# rfid.net
KiCad netlist of a schematic drawn in EAGLE
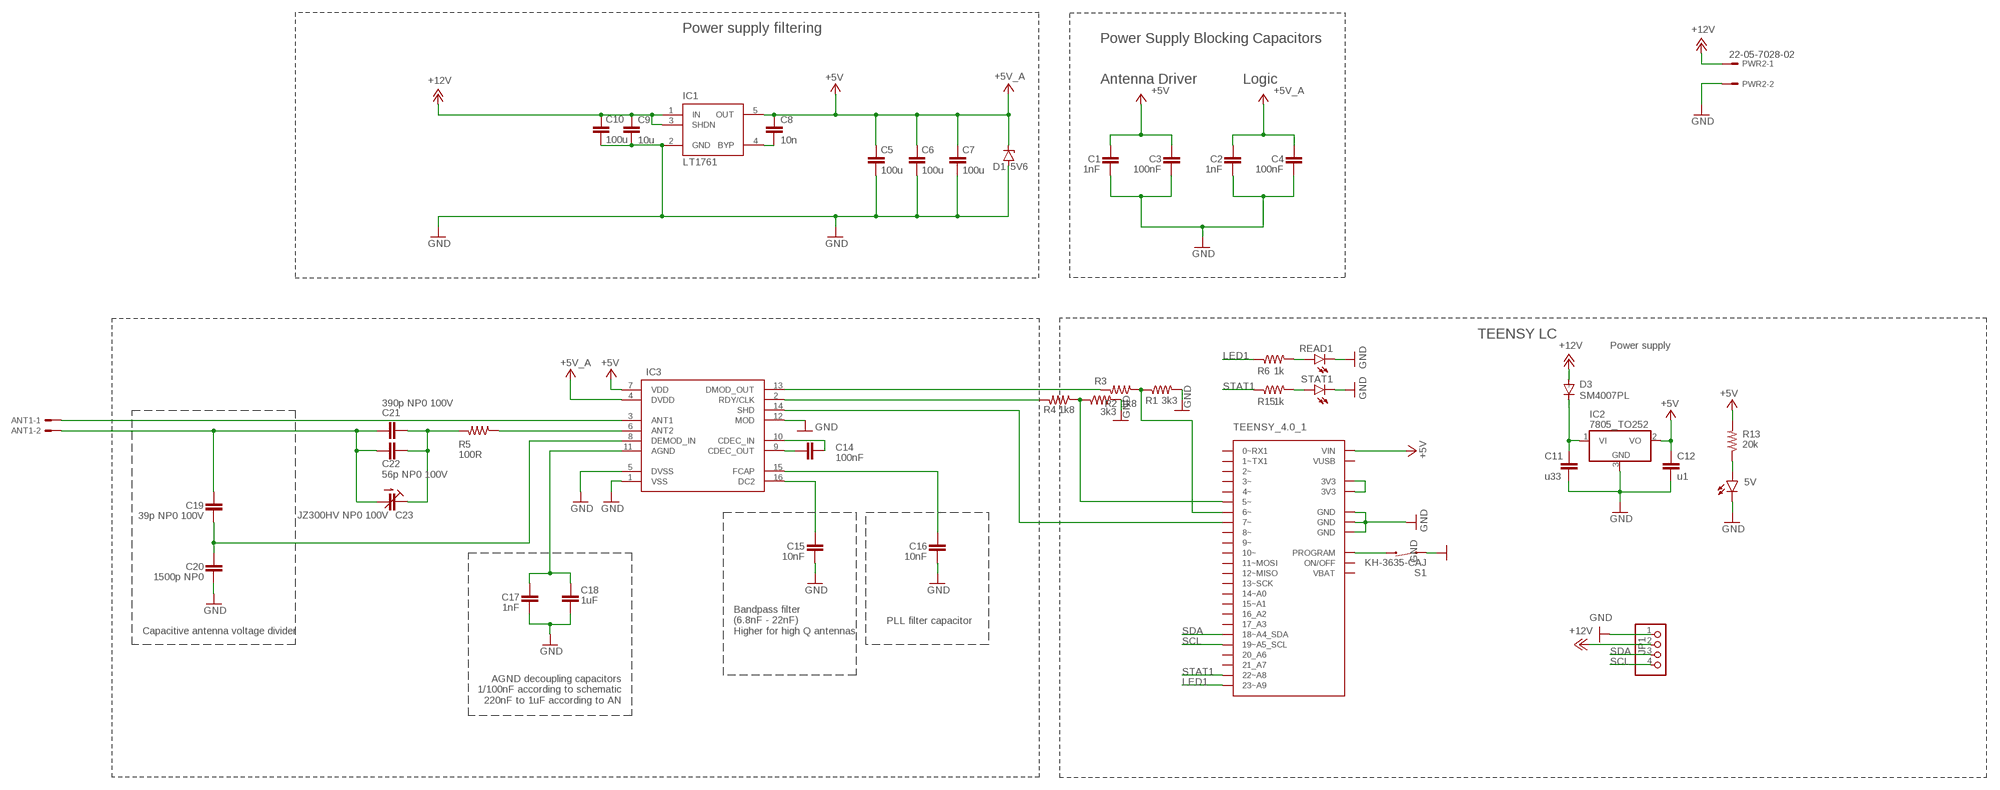
[diagram p0: schematic, sheet 1, part 1 of 2]
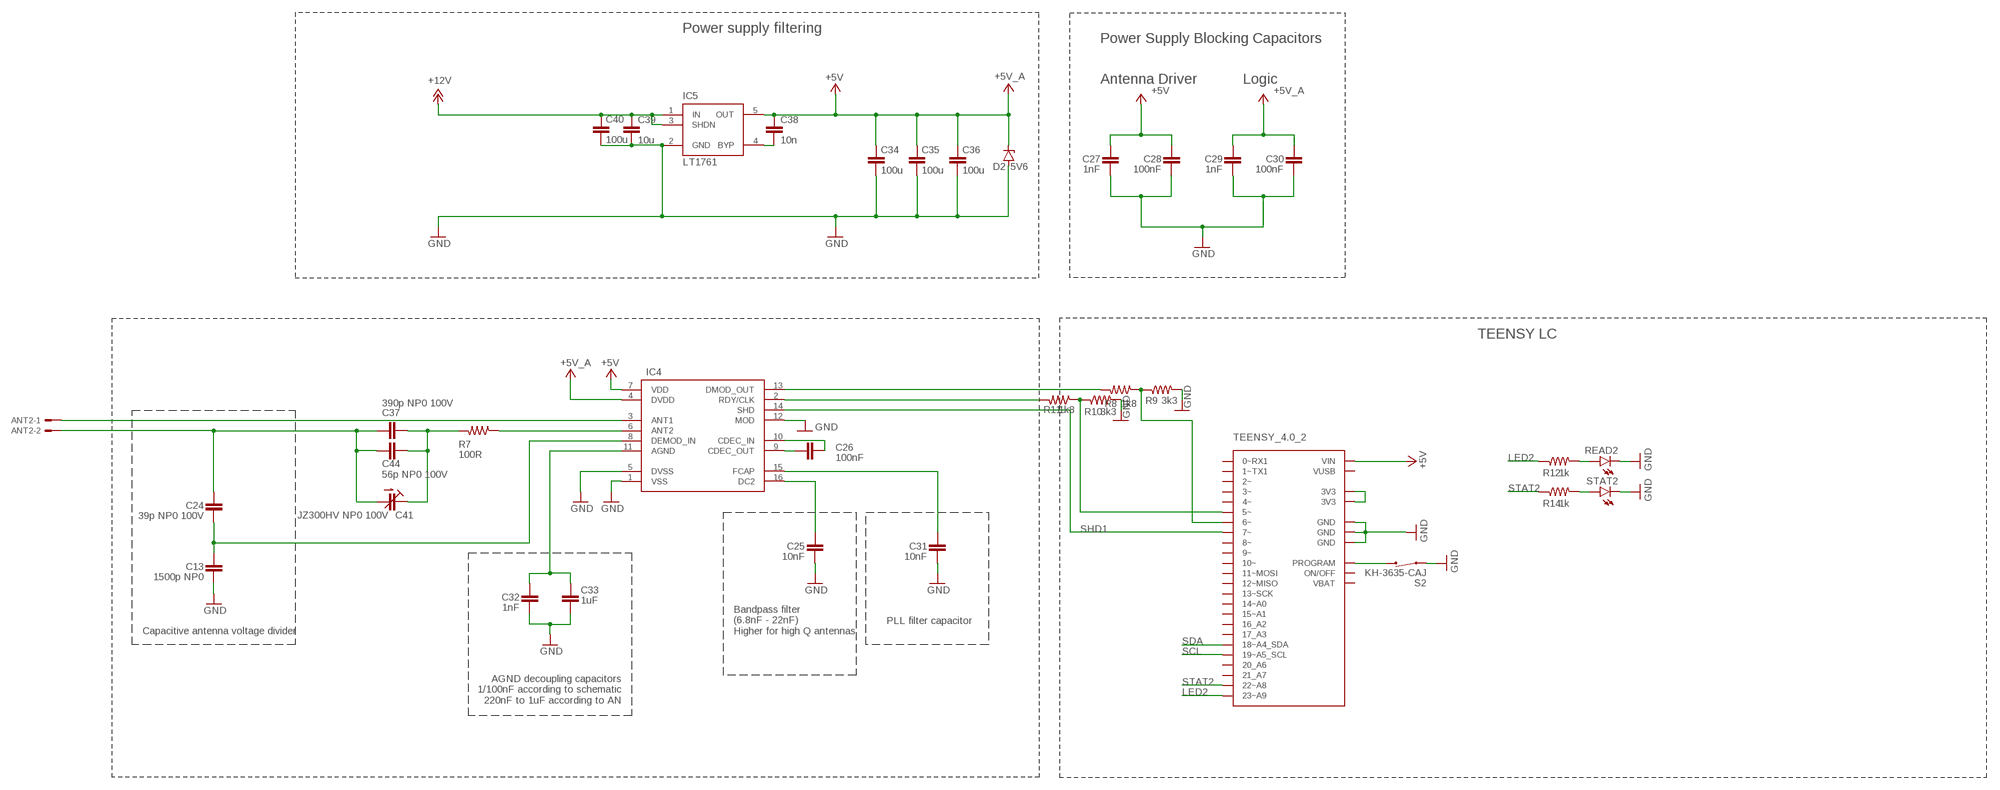
[diagram p1: schematic, sheet 1, part 2 of 2]

(export (version "E")
  (design (tool "Eeschema 10.0.6"))
  (components
    (comp (ref "5V")
      (value "LEDCHIPLED_0805")
      (footprint "eagle-import:CHIPLED_0805")
      (libsource (lib "eagle-import") (part "LEDCHIPLED_0805"))
    )
    (comp (ref "ANT1")
      (value "53261-02")
      (footprint "eagle-import:53261-02")
      (fields (field (name "MF") "MOLEX"))
      (libsource (lib "eagle-import") (part "53?-02261"))
    )
    (comp (ref "ANT2")
      (value "53261-02")
      (footprint "eagle-import:53261-02")
      (fields (field (name "MF") "MOLEX"))
      (libsource (lib "eagle-import") (part "53?-02261"))
    )
    (comp (ref "C1")
      (value "1nF")
      (footprint "eagle-import:R1206")
      (libsource (lib "eagle-import") (part "C1206"))
    )
    (comp (ref "C2")
      (value "1nF")
      (footprint "eagle-import:R1206")
      (libsource (lib "eagle-import") (part "C1206"))
    )
    (comp (ref "C3")
      (value "100nF")
      (footprint "eagle-import:R1206")
      (libsource (lib "eagle-import") (part "C1206"))
    )
    (comp (ref "C4")
      (value "100nF")
      (footprint "eagle-import:R1206")
      (libsource (lib "eagle-import") (part "C1206"))
    )
    (comp (ref "C5")
      (value "100u")
      (footprint "eagle-import:R1206")
      (libsource (lib "eagle-import") (part "C1206"))
    )
    (comp (ref "C6")
      (value "100u")
      (footprint "eagle-import:R1206")
      (libsource (lib "eagle-import") (part "C1206"))
    )
    (comp (ref "C7")
      (value "100u")
      (footprint "eagle-import:R1206")
      (libsource (lib "eagle-import") (part "C1206"))
    )
    (comp (ref "C8")
      (value "10n")
      (footprint "eagle-import:R1206")
      (libsource (lib "eagle-import") (part "C1206"))
    )
    (comp (ref "C9")
      (value "10u")
      (footprint "eagle-import:R1206")
      (libsource (lib "eagle-import") (part "C1206"))
    )
    (comp (ref "C10")
      (value "100u")
      (footprint "eagle-import:R1206")
      (libsource (lib "eagle-import") (part "C1206"))
    )
    (comp (ref "C11")
      (value "u33")
      (footprint "eagle-import:C0805")
      (libsource (lib "eagle-import") (part "C-EUC0805"))
    )
    (comp (ref "C12")
      (value "u1")
      (footprint "eagle-import:C0805")
      (libsource (lib "eagle-import") (part "C-EUC0805"))
    )
    (comp (ref "C13")
      (value "1500p NP0")
      (footprint "eagle-import:R1206")
      (libsource (lib "eagle-import") (part "C1206"))
    )
    (comp (ref "C14")
      (value "100nF")
      (footprint "eagle-import:R1206")
      (libsource (lib "eagle-import") (part "C1206"))
    )
    (comp (ref "C15")
      (value "10nF")
      (footprint "eagle-import:R1206")
      (libsource (lib "eagle-import") (part "C1206"))
    )
    (comp (ref "C16")
      (value "10nF")
      (footprint "eagle-import:R1206")
      (libsource (lib "eagle-import") (part "C1206"))
    )
    (comp (ref "C17")
      (value "1nF")
      (footprint "eagle-import:R1206")
      (libsource (lib "eagle-import") (part "C1206"))
    )
    (comp (ref "C18")
      (value "1uF")
      (footprint "eagle-import:R1206")
      (libsource (lib "eagle-import") (part "C1206"))
    )
    (comp (ref "C19")
      (value "39p NP0 100V")
      (footprint "eagle-import:R1206")
      (libsource (lib "eagle-import") (part "C1206"))
    )
    (comp (ref "C20")
      (value "1500p NP0")
      (footprint "eagle-import:R1206")
      (libsource (lib "eagle-import") (part "C1206"))
    )
    (comp (ref "C21")
      (value "390p NP0 100V")
      (footprint "eagle-import:R1206")
      (libsource (lib "eagle-import") (part "C1206"))
    )
    (comp (ref "C22")
      (value "56p NP0 100V")
      (footprint "eagle-import:R1206")
      (libsource (lib "eagle-import") (part "C1206"))
    )
    (comp (ref "C23")
      (value "JZ300HV NP0 100V")
      (footprint "eagle-import:JZ300HV")
      (libsource (lib "eagle-import") (part "JZ300HV"))
    )
    (comp (ref "C24")
      (value "39p NP0 100V")
      (footprint "eagle-import:R1206")
      (libsource (lib "eagle-import") (part "C1206"))
    )
    (comp (ref "C25")
      (value "10nF")
      (footprint "eagle-import:R1206")
      (libsource (lib "eagle-import") (part "C1206"))
    )
    (comp (ref "C26")
      (value "100nF")
      (footprint "eagle-import:R1206")
      (libsource (lib "eagle-import") (part "C1206"))
    )
    (comp (ref "C27")
      (value "1nF")
      (footprint "eagle-import:R1206")
      (libsource (lib "eagle-import") (part "C1206"))
    )
    (comp (ref "C28")
      (value "100nF")
      (footprint "eagle-import:R1206")
      (libsource (lib "eagle-import") (part "C1206"))
    )
    (comp (ref "C29")
      (value "1nF")
      (footprint "eagle-import:R1206")
      (libsource (lib "eagle-import") (part "C1206"))
    )
    (comp (ref "C30")
      (value "100nF")
      (footprint "eagle-import:R1206")
      (libsource (lib "eagle-import") (part "C1206"))
    )
    (comp (ref "C31")
      (value "10nF")
      (footprint "eagle-import:R1206")
      (libsource (lib "eagle-import") (part "C1206"))
    )
    (comp (ref "C32")
      (value "1nF")
      (footprint "eagle-import:R1206")
      (libsource (lib "eagle-import") (part "C1206"))
    )
    (comp (ref "C33")
      (value "1uF")
      (footprint "eagle-import:R1206")
      (libsource (lib "eagle-import") (part "C1206"))
    )
    (comp (ref "C34")
      (value "100u")
      (footprint "eagle-import:R1206")
      (libsource (lib "eagle-import") (part "C1206"))
    )
    (comp (ref "C35")
      (value "100u")
      (footprint "eagle-import:R1206")
      (libsource (lib "eagle-import") (part "C1206"))
    )
    (comp (ref "C36")
      (value "100u")
      (footprint "eagle-import:R1206")
      (libsource (lib "eagle-import") (part "C1206"))
    )
    (comp (ref "C37")
      (value "390p NP0 100V")
      (footprint "eagle-import:R1206")
      (libsource (lib "eagle-import") (part "C1206"))
    )
    (comp (ref "C38")
      (value "10n")
      (footprint "eagle-import:R1206")
      (libsource (lib "eagle-import") (part "C1206"))
    )
    (comp (ref "C39")
      (value "10u")
      (footprint "eagle-import:R1206")
      (libsource (lib "eagle-import") (part "C1206"))
    )
    (comp (ref "C40")
      (value "100u")
      (footprint "eagle-import:R1206")
      (libsource (lib "eagle-import") (part "C1206"))
    )
    (comp (ref "C41")
      (value "JZ300HV NP0 100V")
      (footprint "eagle-import:JZ300HV")
      (libsource (lib "eagle-import") (part "JZ300HV"))
    )
    (comp (ref "C44")
      (value "56p NP0 100V")
      (footprint "eagle-import:R1206")
      (libsource (lib "eagle-import") (part "C1206"))
    )
    (comp (ref "D1")
      (value "5V6")
      (footprint "eagle-import:SOD80C")
      (libsource (lib "eagle-import") (part "ZENER-DIODESOD80C"))
    )
    (comp (ref "D2")
      (value "5V6")
      (footprint "eagle-import:SOD80C")
      (libsource (lib "eagle-import") (part "ZENER-DIODESOD80C"))
    )
    (comp (ref "D3")
      (value "SM4007PL")
      (footprint "eagle-import:SOD-123_MINI-SMA")
      (libsource (lib "eagle-import") (part "CGRM400-G7"))
    )
    (comp (ref "IC1")
      (value "LT1761")
      (footprint "eagle-import:TSOT23-5")
      (libsource (lib "eagle-import") (part "LT1761"))
    )
    (comp (ref "IC2")
      (value "7805_TO252")
      (footprint "eagle-import:TO252")
      (libsource (lib "eagle-import") (part "7805_TO252"))
    )
    (comp (ref "IC3")
      (value "EM4095")
      (footprint "eagle-import:SO16")
      (libsource (lib "eagle-import") (part "EM4095"))
    )
    (comp (ref "IC4")
      (value "EM4095")
      (footprint "eagle-import:SO16")
      (libsource (lib "eagle-import") (part "EM4095"))
    )
    (comp (ref "IC5")
      (value "LT1761")
      (footprint "eagle-import:TSOT23-5")
      (libsource (lib "eagle-import") (part "LT1761"))
    )
    (comp (ref "JP1")
      (value "PINHD-1X4")
      (footprint "eagle-import:1X04")
      (libsource (lib "eagle-import") (part "PINHD-1X4"))
    )
    (comp (ref "PWR2")
      (value "22-05-7028-02")
      (footprint "eagle-import:7395-02")
      (fields (field (name "MF") "MOLEX"))
      (libsource (lib "eagle-import") (part "22-?-0205-7028"))
    )
    (comp (ref "R1")
      (value "3k3")
      (footprint "eagle-import:R0805")
      (libsource (lib "eagle-import") (part "R-US_R0805"))
    )
    (comp (ref "R2")
      (value "1k8")
      (footprint "eagle-import:R0805")
      (libsource (lib "eagle-import") (part "R-US_R0805"))
    )
    (comp (ref "R3")
      (value "3k3")
      (footprint "eagle-import:R0805")
      (libsource (lib "eagle-import") (part "R-US_R0805"))
    )
    (comp (ref "R4")
      (value "1k8")
      (footprint "eagle-import:R0805")
      (libsource (lib "eagle-import") (part "R-US_R0805"))
    )
    (comp (ref "R5")
      (value "100R")
      (footprint "eagle-import:R1206")
      (libsource (lib "eagle-import") (part "R1206"))
    )
    (comp (ref "R6")
      (value "1k")
      (footprint "eagle-import:R0805")
      (libsource (lib "eagle-import") (part "R-US_R0805"))
    )
    (comp (ref "R7")
      (value "100R")
      (footprint "eagle-import:R1206")
      (libsource (lib "eagle-import") (part "R1206"))
    )
    (comp (ref "R8")
      (value "1k8")
      (footprint "eagle-import:R0805")
      (libsource (lib "eagle-import") (part "R-US_R0805"))
    )
    (comp (ref "R9")
      (value "3k3")
      (footprint "eagle-import:R0805")
      (libsource (lib "eagle-import") (part "R-US_R0805"))
    )
    (comp (ref "R10")
      (value "3k3")
      (footprint "eagle-import:R0805")
      (libsource (lib "eagle-import") (part "R-US_R0805"))
    )
    (comp (ref "R11")
      (value "1k8")
      (footprint "eagle-import:R0805")
      (libsource (lib "eagle-import") (part "R-US_R0805"))
    )
    (comp (ref "R12")
      (value "1k")
      (footprint "eagle-import:R0805")
      (libsource (lib "eagle-import") (part "R-US_R0805"))
    )
    (comp (ref "R13")
      (value "20k")
      (footprint "eagle-import:R0805")
      (libsource (lib "eagle-import") (part "R-US_R0805"))
    )
    (comp (ref "R14")
      (value "1k")
      (footprint "eagle-import:R0805")
      (libsource (lib "eagle-import") (part "R-US_R0805"))
    )
    (comp (ref "R15")
      (value "1k")
      (footprint "eagle-import:R0805")
      (libsource (lib "eagle-import") (part "R-US_R0805"))
    )
    (comp (ref "READ1")
      (value "LEDCHIPLED_0805")
      (footprint "eagle-import:CHIPLED_0805")
      (libsource (lib "eagle-import") (part "LEDCHIPLED_0805"))
    )
    (comp (ref "READ2")
      (value "LEDCHIPLED_0805")
      (footprint "eagle-import:CHIPLED_0805")
      (libsource (lib "eagle-import") (part "LEDCHIPLED_0805"))
    )
    (comp (ref "S1")
      (value "KH-3635-CAJ")
      (footprint "eagle-import:KH-3635-CAJ")
      (libsource (lib "eagle-import") (part "KH-3635-CAJ"))
    )
    (comp (ref "S2")
      (value "KH-3635-CAJ")
      (footprint "eagle-import:KH-3635-CAJ")
      (libsource (lib "eagle-import") (part "KH-3635-CAJ"))
    )
    (comp (ref "STAT1")
      (value "LEDCHIPLED_0805")
      (footprint "eagle-import:CHIPLED_0805")
      (libsource (lib "eagle-import") (part "LEDCHIPLED_0805"))
    )
    (comp (ref "STAT2")
      (value "LEDCHIPLED_0805")
      (footprint "eagle-import:CHIPLED_0805")
      (libsource (lib "eagle-import") (part "LEDCHIPLED_0805"))
    )
    (comp (ref "TEENSY_4.0_1")
      (value "TEENSY40")
      (footprint "eagle-import:TEENSY40")
      (libsource (lib "eagle-import") (part "TEENSY40"))
    )
    (comp (ref "TEENSY_4.0_2")
      (value "TEENSY40")
      (footprint "eagle-import:TEENSY40")
      (libsource (lib "eagle-import") (part "TEENSY40"))
    )
  )
  (nets
    (net (code "1") (name "+5V") (class "Default")
      (node (ref "C1") (pin "2") (pinfunction "2_2") (pintype "passive"))
      (node (ref "C12") (pin "1") (pinfunction "1_1") (pintype "passive"))
      (node (ref "C2") (pin "2") (pinfunction "2_2") (pintype "passive"))
      (node (ref "C27") (pin "2") (pinfunction "2_2") (pintype "passive"))
      (node (ref "C28") (pin "2") (pinfunction "2_2") (pintype "passive"))
      (node (ref "C29") (pin "2") (pinfunction "2_2") (pintype "passive"))
      (node (ref "C3") (pin "2") (pinfunction "2_2") (pintype "passive"))
      (node (ref "C30") (pin "2") (pinfunction "2_2") (pintype "passive"))
      (node (ref "C34") (pin "1") (pinfunction "1_1") (pintype "passive"))
      (node (ref "C35") (pin "1") (pinfunction "1_1") (pintype "passive"))
      (node (ref "C36") (pin "1") (pinfunction "1_1") (pintype "passive"))
      (node (ref "C38") (pin "1") (pinfunction "1_1") (pintype "passive"))
      (node (ref "C4") (pin "2") (pinfunction "2_2") (pintype "passive"))
      (node (ref "C5") (pin "1") (pinfunction "1_1") (pintype "passive"))
      (node (ref "C6") (pin "1") (pinfunction "1_1") (pintype "passive"))
      (node (ref "C7") (pin "1") (pinfunction "1_1") (pintype "passive"))
      (node (ref "C8") (pin "1") (pinfunction "1_1") (pintype "passive"))
      (node (ref "D1") (pin "C") (pinfunction "C_C") (pintype "passive"))
      (node (ref "D2") (pin "C") (pinfunction "C_C") (pintype "passive"))
      (node (ref "IC1") (pin "5") (pinfunction "OUT_5") (pintype "power_in"))
      (node (ref "IC2") (pin "2") (pinfunction "VO_2") (pintype "passive"))
      (node (ref "IC3") (pin "4") (pinfunction "DVDD_4") (pintype "power_in"))
      (node (ref "IC3") (pin "7") (pinfunction "VDD_7") (pintype "power_in"))
      (node (ref "IC4") (pin "4") (pinfunction "DVDD_4") (pintype "power_in"))
      (node (ref "IC4") (pin "7") (pinfunction "VDD_7") (pintype "power_in"))
      (node (ref "IC5") (pin "5") (pinfunction "OUT_5") (pintype "power_in"))
      (node (ref "R13") (pin "2") (pinfunction "2_2") (pintype "passive"))
      (node (ref "TEENSY_4.0_1") (pin "VIN") (pinfunction "VIN_VIN") (pintype "bidirectional"))
      (node (ref "TEENSY_4.0_2") (pin "VIN") (pinfunction "VIN_VIN") (pintype "bidirectional"))
    )
    (net (code "2") (name "+12V") (class "Default")
      (node (ref "C10") (pin "1") (pinfunction "1_1") (pintype "passive"))
      (node (ref "C39") (pin "1") (pinfunction "1_1") (pintype "passive"))
      (node (ref "C40") (pin "1") (pinfunction "1_1") (pintype "passive"))
      (node (ref "C9") (pin "1") (pinfunction "1_1") (pintype "passive"))
      (node (ref "D3") (pin "A") (pinfunction "A_A") (pintype "passive"))
      (node (ref "IC1") (pin "1") (pinfunction "IN_1") (pintype "power_in"))
      (node (ref "IC1") (pin "3") (pinfunction "SHDN_3") (pintype "input"))
      (node (ref "IC5") (pin "1") (pinfunction "IN_1") (pintype "power_in"))
      (node (ref "IC5") (pin "3") (pinfunction "SHDN_3") (pintype "input"))
      (node (ref "JP1") (pin "2") (pinfunction "2_2") (pintype "passive"))
      (node (ref "PWR2") (pin "1") (pinfunction "S_1") (pintype "passive"))
    )
    (net (code "3") (name "/LED1") (class "Default")
      (node (ref "R6") (pin "1") (pinfunction "1_1") (pintype "passive"))
      (node (ref "TEENSY_4.0_1") (pin "23") (pinfunction "23~{A9}_23") (pintype "bidirectional"))
    )
    (net (code "4") (name "/LED2") (class "Default")
      (node (ref "R12") (pin "1") (pinfunction "1_1") (pintype "passive"))
      (node (ref "TEENSY_4.0_2") (pin "23") (pinfunction "23~{A9}_23") (pintype "bidirectional"))
    )
    (net (code "5") (name "/SCL") (class "Default")
      (node (ref "JP1") (pin "4") (pinfunction "4_4") (pintype "passive"))
      (node (ref "TEENSY_4.0_1") (pin "19") (pinfunction "19~{A5_SCL}_19") (pintype "bidirectional"))
      (node (ref "TEENSY_4.0_2") (pin "19") (pinfunction "19~{A5_SCL}_19") (pintype "bidirectional"))
    )
    (net (code "6") (name "/SDA") (class "Default")
      (node (ref "JP1") (pin "3") (pinfunction "3_3") (pintype "passive"))
      (node (ref "TEENSY_4.0_1") (pin "18") (pinfunction "18~{A4_SDA}_18") (pintype "bidirectional"))
      (node (ref "TEENSY_4.0_2") (pin "18") (pinfunction "18~{A4_SDA}_18") (pintype "bidirectional"))
    )
    (net (code "7") (name "/SHD1") (class "Default")
      (node (ref "IC4") (pin "14") (pinfunction "SHD_14") (pintype "input"))
      (node (ref "TEENSY_4.0_2") (pin "7") (pinfunction "7~{}_7") (pintype "bidirectional"))
    )
    (net (code "8") (name "/STAT1") (class "Default")
      (node (ref "R15") (pin "1") (pinfunction "1_1") (pintype "passive"))
      (node (ref "TEENSY_4.0_1") (pin "22") (pinfunction "22~{A8}_22") (pintype "bidirectional"))
    )
    (net (code "9") (name "/STAT2") (class "Default")
      (node (ref "R14") (pin "1") (pinfunction "1_1") (pintype "passive"))
      (node (ref "TEENSY_4.0_2") (pin "22") (pinfunction "22~{A8}_22") (pintype "bidirectional"))
    )
    (net (code "10") (name "GND") (class "Default")
      (node (ref "5V") (pin "C") (pinfunction "C_C") (pintype "passive"))
      (node (ref "C1") (pin "1") (pinfunction "1_1") (pintype "passive"))
      (node (ref "C10") (pin "2") (pinfunction "2_2") (pintype "passive"))
      (node (ref "C11") (pin "2") (pinfunction "2_2") (pintype "passive"))
      (node (ref "C12") (pin "2") (pinfunction "2_2") (pintype "passive"))
      (node (ref "C13") (pin "1") (pinfunction "1_1") (pintype "passive"))
      (node (ref "C15") (pin "2") (pinfunction "2_2") (pintype "passive"))
      (node (ref "C16") (pin "2") (pinfunction "2_2") (pintype "passive"))
      (node (ref "C17") (pin "1") (pinfunction "1_1") (pintype "passive"))
      (node (ref "C18") (pin "1") (pinfunction "1_1") (pintype "passive"))
      (node (ref "C2") (pin "1") (pinfunction "1_1") (pintype "passive"))
      (node (ref "C20") (pin "1") (pinfunction "1_1") (pintype "passive"))
      (node (ref "C25") (pin "2") (pinfunction "2_2") (pintype "passive"))
      (node (ref "C27") (pin "1") (pinfunction "1_1") (pintype "passive"))
      (node (ref "C28") (pin "1") (pinfunction "1_1") (pintype "passive"))
      (node (ref "C29") (pin "1") (pinfunction "1_1") (pintype "passive"))
      (node (ref "C3") (pin "1") (pinfunction "1_1") (pintype "passive"))
      (node (ref "C30") (pin "1") (pinfunction "1_1") (pintype "passive"))
      (node (ref "C31") (pin "2") (pinfunction "2_2") (pintype "passive"))
      (node (ref "C32") (pin "1") (pinfunction "1_1") (pintype "passive"))
      (node (ref "C33") (pin "1") (pinfunction "1_1") (pintype "passive"))
      (node (ref "C34") (pin "2") (pinfunction "2_2") (pintype "passive"))
      (node (ref "C35") (pin "2") (pinfunction "2_2") (pintype "passive"))
      (node (ref "C36") (pin "2") (pinfunction "2_2") (pintype "passive"))
      (node (ref "C39") (pin "2") (pinfunction "2_2") (pintype "passive"))
      (node (ref "C4") (pin "1") (pinfunction "1_1") (pintype "passive"))
      (node (ref "C40") (pin "2") (pinfunction "2_2") (pintype "passive"))
      (node (ref "C5") (pin "2") (pinfunction "2_2") (pintype "passive"))
      (node (ref "C6") (pin "2") (pinfunction "2_2") (pintype "passive"))
      (node (ref "C7") (pin "2") (pinfunction "2_2") (pintype "passive"))
      (node (ref "C9") (pin "2") (pinfunction "2_2") (pintype "passive"))
      (node (ref "D1") (pin "A") (pinfunction "A_A") (pintype "passive"))
      (node (ref "D2") (pin "A") (pinfunction "A_A") (pintype "passive"))
      (node (ref "IC1") (pin "2") (pinfunction "GND_2") (pintype "power_in"))
      (node (ref "IC2") (pin "3") (pinfunction "GND_3") (pintype "passive"))
      (node (ref "IC3") (pin "1") (pinfunction "VSS_1") (pintype "power_in"))
      (node (ref "IC3") (pin "12") (pinfunction "MOD_12") (pintype "input"))
      (node (ref "IC3") (pin "5") (pinfunction "DVSS_5") (pintype "power_in"))
      (node (ref "IC4") (pin "1") (pinfunction "VSS_1") (pintype "power_in"))
      (node (ref "IC4") (pin "12") (pinfunction "MOD_12") (pintype "input"))
      (node (ref "IC4") (pin "5") (pinfunction "DVSS_5") (pintype "power_in"))
      (node (ref "IC5") (pin "2") (pinfunction "GND_2") (pintype "power_in"))
      (node (ref "JP1") (pin "1") (pinfunction "1_1") (pintype "passive"))
      (node (ref "PWR2") (pin "2") (pinfunction "S_2") (pintype "passive"))
      (node (ref "R1") (pin "2") (pinfunction "2_2") (pintype "passive"))
      (node (ref "R10") (pin "2") (pinfunction "2_2") (pintype "passive"))
      (node (ref "R3") (pin "2") (pinfunction "2_2") (pintype "passive"))
      (node (ref "R9") (pin "2") (pinfunction "2_2") (pintype "passive"))
      (node (ref "READ1") (pin "C") (pinfunction "C_C") (pintype "passive"))
      (node (ref "READ2") (pin "C") (pinfunction "C_C") (pintype "passive"))
      (node (ref "S1") (pin "P$1") (pinfunction "1_P$1") (pintype "passive"))
      (node (ref "S2") (pin "P$1") (pinfunction "1_P$1") (pintype "passive"))
      (node (ref "STAT1") (pin "C") (pinfunction "C_C") (pintype "passive"))
      (node (ref "STAT2") (pin "C") (pinfunction "C_C") (pintype "passive"))
      (node (ref "TEENSY_4.0_1") (pin "GND") (pinfunction "GND_GND") (pintype "bidirectional"))
      (node (ref "TEENSY_4.0_1") (pin "GND@1") (pinfunction "GND_GND@1") (pintype "bidirectional"))
      (node (ref "TEENSY_4.0_1") (pin "GND@2") (pinfunction "GND_GND@2") (pintype "bidirectional"))
      (node (ref "TEENSY_4.0_2") (pin "GND") (pinfunction "GND_GND") (pintype "bidirectional"))
      (node (ref "TEENSY_4.0_2") (pin "GND@1") (pinfunction "GND_GND@1") (pintype "bidirectional"))
      (node (ref "TEENSY_4.0_2") (pin "GND@2") (pinfunction "GND_GND@2") (pintype "bidirectional"))
    )
    (net (code "11") (name "Net-(5V-PadA)") (class "Default")
      (node (ref "5V") (pin "A") (pinfunction "A_A") (pintype "passive"))
      (node (ref "R13") (pin "1") (pinfunction "1_1") (pintype "passive"))
    )
    (net (code "12") (name "Net-(ANT1A-S)") (class "Default")
      (node (ref "ANT1") (pin "1") (pinfunction "S_1") (pintype "passive"))
      (node (ref "IC3") (pin "3") (pinfunction "ANT1_3") (pintype "output"))
    )
    (net (code "13") (name "Net-(ANT1B-S)") (class "Default")
      (node (ref "ANT1") (pin "2") (pinfunction "S_2") (pintype "passive"))
      (node (ref "C19") (pin "2") (pinfunction "2_2") (pintype "passive"))
      (node (ref "C21") (pin "1") (pinfunction "1_1") (pintype "passive"))
      (node (ref "C22") (pin "1") (pinfunction "1_1") (pintype "passive"))
      (node (ref "C23") (pin "P$1") (pinfunction "A_P$1") (pintype "passive"))
    )
    (net (code "14") (name "Net-(ANT2A-S)") (class "Default")
      (node (ref "ANT2") (pin "1") (pinfunction "S_1") (pintype "passive"))
      (node (ref "IC4") (pin "3") (pinfunction "ANT1_3") (pintype "output"))
    )
    (net (code "15") (name "Net-(ANT2B-S)") (class "Default")
      (node (ref "ANT2") (pin "2") (pinfunction "S_2") (pintype "passive"))
      (node (ref "C24") (pin "2") (pinfunction "2_2") (pintype "passive"))
      (node (ref "C37") (pin "1") (pinfunction "1_1") (pintype "passive"))
      (node (ref "C41") (pin "P$1") (pinfunction "A_P$1") (pintype "passive"))
      (node (ref "C44") (pin "1") (pinfunction "1_1") (pintype "passive"))
    )
    (net (code "16") (name "Net-(C23-E)") (class "Default")
      (node (ref "C21") (pin "2") (pinfunction "2_2") (pintype "passive"))
      (node (ref "C22") (pin "2") (pinfunction "2_2") (pintype "passive"))
      (node (ref "C23") (pin "P$2") (pinfunction "E_P$2") (pintype "passive"))
      (node (ref "R5") (pin "2") (pinfunction "2_2") (pintype "passive"))
    )
    (net (code "17") (name "Net-(C41-E)") (class "Default")
      (node (ref "C37") (pin "2") (pinfunction "2_2") (pintype "passive"))
      (node (ref "C41") (pin "P$2") (pinfunction "E_P$2") (pintype "passive"))
      (node (ref "C44") (pin "2") (pinfunction "2_2") (pintype "passive"))
      (node (ref "R7") (pin "2") (pinfunction "2_2") (pintype "passive"))
    )
    (net (code "18") (name "Net-(IC1-BYP)") (class "Default")
      (node (ref "C8") (pin "2") (pinfunction "2_2") (pintype "passive"))
      (node (ref "IC1") (pin "4") (pinfunction "BYP_4") (pintype "input"))
    )
    (net (code "19") (name "Net-(IC2-VI)") (class "Default")
      (node (ref "C11") (pin "1") (pinfunction "1_1") (pintype "passive"))
      (node (ref "D3") (pin "C") (pinfunction "C_C") (pintype "passive"))
      (node (ref "IC2") (pin "1") (pinfunction "VI_1") (pintype "input"))
    )
    (net (code "20") (name "Net-(IC3-AGND)") (class "Default")
      (node (ref "C17") (pin "2") (pinfunction "2_2") (pintype "passive"))
      (node (ref "C18") (pin "2") (pinfunction "2_2") (pintype "passive"))
      (node (ref "IC3") (pin "11") (pinfunction "AGND_11") (pintype "power_in"))
    )
    (net (code "21") (name "Net-(IC3-ANT2)") (class "Default")
      (node (ref "IC3") (pin "6") (pinfunction "ANT2_6") (pintype "output"))
      (node (ref "R5") (pin "1") (pinfunction "1_1") (pintype "passive"))
    )
    (net (code "22") (name "Net-(IC3-CDEC_IN)") (class "Default")
      (node (ref "C14") (pin "2") (pinfunction "2_2") (pintype "passive"))
      (node (ref "IC3") (pin "10") (pinfunction "CDEC_IN_10") (pintype "input"))
    )
    (net (code "23") (name "Net-(IC3-CDEC_OUT)") (class "Default")
      (node (ref "C14") (pin "1") (pinfunction "1_1") (pintype "passive"))
      (node (ref "IC3") (pin "9") (pinfunction "CDEC_OUT_9") (pintype "output"))
    )
    (net (code "24") (name "Net-(IC3-DC2)") (class "Default")
      (node (ref "C15") (pin "1") (pinfunction "1_1") (pintype "passive"))
      (node (ref "IC3") (pin "16") (pinfunction "DC2_16") (pintype "power_in"))
    )
    (net (code "25") (name "Net-(IC3-DEMOD_IN)") (class "Default")
      (node (ref "C19") (pin "1") (pinfunction "1_1") (pintype "passive"))
      (node (ref "C20") (pin "2") (pinfunction "2_2") (pintype "passive"))
      (node (ref "IC3") (pin "8") (pinfunction "DEMOD_IN_8") (pintype "input"))
    )
    (net (code "26") (name "Net-(IC3-DMOD_OUT)") (class "Default")
      (node (ref "IC3") (pin "13") (pinfunction "DMOD_OUT_13") (pintype "output"))
      (node (ref "R2") (pin "2") (pinfunction "2_2") (pintype "passive"))
    )
    (net (code "27") (name "Net-(IC3-FCAP)") (class "Default")
      (node (ref "C16") (pin "1") (pinfunction "1_1") (pintype "passive"))
      (node (ref "IC3") (pin "15") (pinfunction "FCAP_15") (pintype "input"))
    )
    (net (code "28") (name "Net-(IC3-RDY{slash}CLK)") (class "Default")
      (node (ref "IC3") (pin "2") (pinfunction "RDY/CLK_2") (pintype "output"))
      (node (ref "R4") (pin "2") (pinfunction "2_2") (pintype "passive"))
    )
    (net (code "29") (name "Net-(IC3-SHD)") (class "Default")
      (node (ref "IC3") (pin "14") (pinfunction "SHD_14") (pintype "input"))
      (node (ref "TEENSY_4.0_1") (pin "7") (pinfunction "7~{}_7") (pintype "bidirectional"))
    )
    (net (code "30") (name "Net-(IC4-AGND)") (class "Default")
      (node (ref "C32") (pin "2") (pinfunction "2_2") (pintype "passive"))
      (node (ref "C33") (pin "2") (pinfunction "2_2") (pintype "passive"))
      (node (ref "IC4") (pin "11") (pinfunction "AGND_11") (pintype "power_in"))
    )
    (net (code "31") (name "Net-(IC4-ANT2)") (class "Default")
      (node (ref "IC4") (pin "6") (pinfunction "ANT2_6") (pintype "output"))
      (node (ref "R7") (pin "1") (pinfunction "1_1") (pintype "passive"))
    )
    (net (code "32") (name "Net-(IC4-CDEC_IN)") (class "Default")
      (node (ref "C26") (pin "2") (pinfunction "2_2") (pintype "passive"))
      (node (ref "IC4") (pin "10") (pinfunction "CDEC_IN_10") (pintype "input"))
    )
    (net (code "33") (name "Net-(IC4-CDEC_OUT)") (class "Default")
      (node (ref "C26") (pin "1") (pinfunction "1_1") (pintype "passive"))
      (node (ref "IC4") (pin "9") (pinfunction "CDEC_OUT_9") (pintype "output"))
    )
    (net (code "34") (name "Net-(IC4-DC2)") (class "Default")
      (node (ref "C25") (pin "1") (pinfunction "1_1") (pintype "passive"))
      (node (ref "IC4") (pin "16") (pinfunction "DC2_16") (pintype "power_in"))
    )
    (net (code "35") (name "Net-(IC4-DEMOD_IN)") (class "Default")
      (node (ref "C13") (pin "2") (pinfunction "2_2") (pintype "passive"))
      (node (ref "C24") (pin "1") (pinfunction "1_1") (pintype "passive"))
      (node (ref "IC4") (pin "8") (pinfunction "DEMOD_IN_8") (pintype "input"))
    )
    (net (code "36") (name "Net-(IC4-DMOD_OUT)") (class "Default")
      (node (ref "IC4") (pin "13") (pinfunction "DMOD_OUT_13") (pintype "output"))
      (node (ref "R8") (pin "2") (pinfunction "2_2") (pintype "passive"))
    )
    (net (code "37") (name "Net-(IC4-FCAP)") (class "Default")
      (node (ref "C31") (pin "1") (pinfunction "1_1") (pintype "passive"))
      (node (ref "IC4") (pin "15") (pinfunction "FCAP_15") (pintype "input"))
    )
    (net (code "38") (name "Net-(IC4-RDY{slash}CLK)") (class "Default")
      (node (ref "IC4") (pin "2") (pinfunction "RDY/CLK_2") (pintype "output"))
      (node (ref "R11") (pin "2") (pinfunction "2_2") (pintype "passive"))
    )
    (net (code "39") (name "Net-(IC5-BYP)") (class "Default")
      (node (ref "C38") (pin "2") (pinfunction "2_2") (pintype "passive"))
      (node (ref "IC5") (pin "4") (pinfunction "BYP_4") (pintype "input"))
    )
    (net (code "40") (name "Net-(R6-Pad2)") (class "Default")
      (node (ref "R6") (pin "2") (pinfunction "2_2") (pintype "passive"))
      (node (ref "READ1") (pin "A") (pinfunction "A_A") (pintype "passive"))
    )
    (net (code "41") (name "Net-(R12-Pad2)") (class "Default")
      (node (ref "R12") (pin "2") (pinfunction "2_2") (pintype "passive"))
      (node (ref "READ2") (pin "A") (pinfunction "A_A") (pintype "passive"))
    )
    (net (code "42") (name "Net-(R14-Pad2)") (class "Default")
      (node (ref "R14") (pin "2") (pinfunction "2_2") (pintype "passive"))
      (node (ref "STAT2") (pin "A") (pinfunction "A_A") (pintype "passive"))
    )
    (net (code "43") (name "Net-(R15-Pad2)") (class "Default")
      (node (ref "R15") (pin "2") (pinfunction "2_2") (pintype "passive"))
      (node (ref "STAT1") (pin "A") (pinfunction "A_A") (pintype "passive"))
    )
    (net (code "44") (name "Net-(S1-2)") (class "Default")
      (node (ref "S1") (pin "P$2") (pinfunction "2_P$2") (pintype "passive"))
      (node (ref "TEENSY_4.0_1") (pin "PROG") (pinfunction "PROGRAM_PROG") (pintype "bidirectional"))
    )
    (net (code "45") (name "Net-(S2-2)") (class "Default")
      (node (ref "S2") (pin "P$2") (pinfunction "2_P$2") (pintype "passive"))
      (node (ref "TEENSY_4.0_2") (pin "PROG") (pinfunction "PROGRAM_PROG") (pintype "bidirectional"))
    )
    (net (code "46") (name "Net-(TEENSY_4.0_1-3V3-Pad3V3@2)") (class "Default")
      (node (ref "TEENSY_4.0_1") (pin "3V3") (pinfunction "3V3_3V3") (pintype "bidirectional"))
      (node (ref "TEENSY_4.0_1") (pin "3V3@2") (pinfunction "3V3_3V3@2") (pintype "bidirectional"))
    )
    (net (code "47") (name "Net-(TEENSY_4.0_1-5~{})") (class "Default")
      (node (ref "R3") (pin "1") (pinfunction "1_1") (pintype "passive"))
      (node (ref "R4") (pin "1") (pinfunction "1_1") (pintype "passive"))
      (node (ref "TEENSY_4.0_1") (pin "5") (pinfunction "5~{}_5") (pintype "bidirectional"))
    )
    (net (code "48") (name "Net-(TEENSY_4.0_1-6~{})") (class "Default")
      (node (ref "R1") (pin "1") (pinfunction "1_1") (pintype "passive"))
      (node (ref "R2") (pin "1") (pinfunction "1_1") (pintype "passive"))
      (node (ref "TEENSY_4.0_1") (pin "6") (pinfunction "6~{}_6") (pintype "bidirectional"))
    )
    (net (code "49") (name "Net-(TEENSY_4.0_2-3V3-Pad3V3@2)") (class "Default")
      (node (ref "TEENSY_4.0_2") (pin "3V3") (pinfunction "3V3_3V3") (pintype "bidirectional"))
      (node (ref "TEENSY_4.0_2") (pin "3V3@2") (pinfunction "3V3_3V3@2") (pintype "bidirectional"))
    )
    (net (code "50") (name "Net-(TEENSY_4.0_2-5~{})") (class "Default")
      (node (ref "R10") (pin "1") (pinfunction "1_1") (pintype "passive"))
      (node (ref "R11") (pin "1") (pinfunction "1_1") (pintype "passive"))
      (node (ref "TEENSY_4.0_2") (pin "5") (pinfunction "5~{}_5") (pintype "bidirectional"))
    )
    (net (code "51") (name "Net-(TEENSY_4.0_2-6~{})") (class "Default")
      (node (ref "R8") (pin "1") (pinfunction "1_1") (pintype "passive"))
      (node (ref "R9") (pin "1") (pinfunction "1_1") (pintype "passive"))
      (node (ref "TEENSY_4.0_2") (pin "6") (pinfunction "6~{}_6") (pintype "bidirectional"))
    )
    (net (code "52") (name "unconnected-(TEENSY_4.0_1-0~{RX1}-Pad0)") (class "Default")
      (node (ref "TEENSY_4.0_1") (pin "0") (pinfunction "0~{RX1}_0") (pintype "bidirectional"))
    )
    (net (code "53") (name "unconnected-(TEENSY_4.0_1-1~{TX1}-Pad1)") (class "Default")
      (node (ref "TEENSY_4.0_1") (pin "1") (pinfunction "1~{TX1}_1") (pintype "bidirectional"))
    )
    (net (code "54") (name "unconnected-(TEENSY_4.0_1-2~{}-Pad2)") (class "Default")
      (node (ref "TEENSY_4.0_1") (pin "2") (pinfunction "2~{}_2") (pintype "bidirectional"))
    )
    (net (code "55") (name "unconnected-(TEENSY_4.0_1-3~{}-Pad3)") (class "Default")
      (node (ref "TEENSY_4.0_1") (pin "3") (pinfunction "3~{}_3") (pintype "bidirectional"))
    )
    (net (code "56") (name "unconnected-(TEENSY_4.0_1-4~{}-Pad4)") (class "Default")
      (node (ref "TEENSY_4.0_1") (pin "4") (pinfunction "4~{}_4") (pintype "bidirectional"))
    )
    (net (code "57") (name "unconnected-(TEENSY_4.0_1-8~{}-Pad8)") (class "Default")
      (node (ref "TEENSY_4.0_1") (pin "8") (pinfunction "8~{}_8") (pintype "bidirectional"))
    )
    (net (code "58") (name "unconnected-(TEENSY_4.0_1-9~{}-Pad9)") (class "Default")
      (node (ref "TEENSY_4.0_1") (pin "9") (pinfunction "9~{}_9") (pintype "bidirectional"))
    )
    (net (code "59") (name "unconnected-(TEENSY_4.0_1-10~{}-Pad10)") (class "Default")
      (node (ref "TEENSY_4.0_1") (pin "10") (pinfunction "10~{}_10") (pintype "bidirectional"))
    )
    (net (code "60") (name "unconnected-(TEENSY_4.0_1-11~{MOSI}-Pad11)") (class "Default")
      (node (ref "TEENSY_4.0_1") (pin "11") (pinfunction "11~{MOSI}_11") (pintype "bidirectional"))
    )
    (net (code "61") (name "unconnected-(TEENSY_4.0_1-12~{MISO}-Pad12)") (class "Default")
      (node (ref "TEENSY_4.0_1") (pin "12") (pinfunction "12~{MISO}_12") (pintype "bidirectional"))
    )
    (net (code "62") (name "unconnected-(TEENSY_4.0_1-13~{SCK}-Pad13)") (class "Default")
      (node (ref "TEENSY_4.0_1") (pin "13") (pinfunction "13~{SCK}_13") (pintype "bidirectional"))
    )
    (net (code "63") (name "unconnected-(TEENSY_4.0_1-14~{A0}-Pad14)") (class "Default")
      (node (ref "TEENSY_4.0_1") (pin "14") (pinfunction "14~{A0}_14") (pintype "bidirectional"))
    )
    (net (code "64") (name "unconnected-(TEENSY_4.0_1-15~{A1}-Pad15)") (class "Default")
      (node (ref "TEENSY_4.0_1") (pin "15") (pinfunction "15~{A1}_15") (pintype "bidirectional"))
    )
    (net (code "65") (name "unconnected-(TEENSY_4.0_1-16_A2-Pad16)") (class "Default")
      (node (ref "TEENSY_4.0_1") (pin "16") (pinfunction "16_A2_16") (pintype "bidirectional"))
    )
    (net (code "66") (name "unconnected-(TEENSY_4.0_1-17_A3-Pad17)") (class "Default")
      (node (ref "TEENSY_4.0_1") (pin "17") (pinfunction "17_A3_17") (pintype "bidirectional"))
    )
    (net (code "67") (name "unconnected-(TEENSY_4.0_1-20_A6-Pad20)") (class "Default")
      (node (ref "TEENSY_4.0_1") (pin "20") (pinfunction "20_A6_20") (pintype "bidirectional"))
    )
    (net (code "68") (name "unconnected-(TEENSY_4.0_1-21_A7-Pad21)") (class "Default")
      (node (ref "TEENSY_4.0_1") (pin "21") (pinfunction "21_A7_21") (pintype "bidirectional"))
    )
    (net (code "69") (name "unconnected-(TEENSY_4.0_1-PadON{slash}OFF)") (class "Default")
      (node (ref "TEENSY_4.0_1") (pin "ON/OFF") (pinfunction "ON/OFF_ON/OFF") (pintype "bidirectional"))
    )
    (net (code "70") (name "unconnected-(TEENSY_4.0_1-PadVBAT)") (class "Default")
      (node (ref "TEENSY_4.0_1") (pin "VBAT") (pinfunction "VBAT_VBAT") (pintype "bidirectional"))
    )
    (net (code "71") (name "unconnected-(TEENSY_4.0_1-PadVUSB)") (class "Default")
      (node (ref "TEENSY_4.0_1") (pin "VUSB") (pinfunction "VUSB_VUSB") (pintype "bidirectional"))
    )
    (net (code "72") (name "unconnected-(TEENSY_4.0_2-0~{RX1}-Pad0)") (class "Default")
      (node (ref "TEENSY_4.0_2") (pin "0") (pinfunction "0~{RX1}_0") (pintype "bidirectional"))
    )
    (net (code "73") (name "unconnected-(TEENSY_4.0_2-1~{TX1}-Pad1)") (class "Default")
      (node (ref "TEENSY_4.0_2") (pin "1") (pinfunction "1~{TX1}_1") (pintype "bidirectional"))
    )
    (net (code "74") (name "unconnected-(TEENSY_4.0_2-2~{}-Pad2)") (class "Default")
      (node (ref "TEENSY_4.0_2") (pin "2") (pinfunction "2~{}_2") (pintype "bidirectional"))
    )
    (net (code "75") (name "unconnected-(TEENSY_4.0_2-3~{}-Pad3)") (class "Default")
      (node (ref "TEENSY_4.0_2") (pin "3") (pinfunction "3~{}_3") (pintype "bidirectional"))
    )
    (net (code "76") (name "unconnected-(TEENSY_4.0_2-4~{}-Pad4)") (class "Default")
      (node (ref "TEENSY_4.0_2") (pin "4") (pinfunction "4~{}_4") (pintype "bidirectional"))
    )
    (net (code "77") (name "unconnected-(TEENSY_4.0_2-8~{}-Pad8)") (class "Default")
      (node (ref "TEENSY_4.0_2") (pin "8") (pinfunction "8~{}_8") (pintype "bidirectional"))
    )
    (net (code "78") (name "unconnected-(TEENSY_4.0_2-9~{}-Pad9)") (class "Default")
      (node (ref "TEENSY_4.0_2") (pin "9") (pinfunction "9~{}_9") (pintype "bidirectional"))
    )
    (net (code "79") (name "unconnected-(TEENSY_4.0_2-10~{}-Pad10)") (class "Default")
      (node (ref "TEENSY_4.0_2") (pin "10") (pinfunction "10~{}_10") (pintype "bidirectional"))
    )
    (net (code "80") (name "unconnected-(TEENSY_4.0_2-11~{MOSI}-Pad11)") (class "Default")
      (node (ref "TEENSY_4.0_2") (pin "11") (pinfunction "11~{MOSI}_11") (pintype "bidirectional"))
    )
    (net (code "81") (name "unconnected-(TEENSY_4.0_2-12~{MISO}-Pad12)") (class "Default")
      (node (ref "TEENSY_4.0_2") (pin "12") (pinfunction "12~{MISO}_12") (pintype "bidirectional"))
    )
    (net (code "82") (name "unconnected-(TEENSY_4.0_2-13~{SCK}-Pad13)") (class "Default")
      (node (ref "TEENSY_4.0_2") (pin "13") (pinfunction "13~{SCK}_13") (pintype "bidirectional"))
    )
    (net (code "83") (name "unconnected-(TEENSY_4.0_2-14~{A0}-Pad14)") (class "Default")
      (node (ref "TEENSY_4.0_2") (pin "14") (pinfunction "14~{A0}_14") (pintype "bidirectional"))
    )
    (net (code "84") (name "unconnected-(TEENSY_4.0_2-15~{A1}-Pad15)") (class "Default")
      (node (ref "TEENSY_4.0_2") (pin "15") (pinfunction "15~{A1}_15") (pintype "bidirectional"))
    )
    (net (code "85") (name "unconnected-(TEENSY_4.0_2-16_A2-Pad16)") (class "Default")
      (node (ref "TEENSY_4.0_2") (pin "16") (pinfunction "16_A2_16") (pintype "bidirectional"))
    )
    (net (code "86") (name "unconnected-(TEENSY_4.0_2-17_A3-Pad17)") (class "Default")
      (node (ref "TEENSY_4.0_2") (pin "17") (pinfunction "17_A3_17") (pintype "bidirectional"))
    )
    (net (code "87") (name "unconnected-(TEENSY_4.0_2-20_A6-Pad20)") (class "Default")
      (node (ref "TEENSY_4.0_2") (pin "20") (pinfunction "20_A6_20") (pintype "bidirectional"))
    )
    (net (code "88") (name "unconnected-(TEENSY_4.0_2-21_A7-Pad21)") (class "Default")
      (node (ref "TEENSY_4.0_2") (pin "21") (pinfunction "21_A7_21") (pintype "bidirectional"))
    )
    (net (code "89") (name "unconnected-(TEENSY_4.0_2-PadON{slash}OFF)") (class "Default")
      (node (ref "TEENSY_4.0_2") (pin "ON/OFF") (pinfunction "ON/OFF_ON/OFF") (pintype "bidirectional"))
    )
    (net (code "90") (name "unconnected-(TEENSY_4.0_2-PadVBAT)") (class "Default")
      (node (ref "TEENSY_4.0_2") (pin "VBAT") (pinfunction "VBAT_VBAT") (pintype "bidirectional"))
    )
    (net (code "91") (name "unconnected-(TEENSY_4.0_2-PadVUSB)") (class "Default")
      (node (ref "TEENSY_4.0_2") (pin "VUSB") (pinfunction "VUSB_VUSB") (pintype "bidirectional"))
    )
  )
)
